# UAF42_AD620___AD8138.net
KiCad netlist of a schematic drawn in EasyEDA Pro
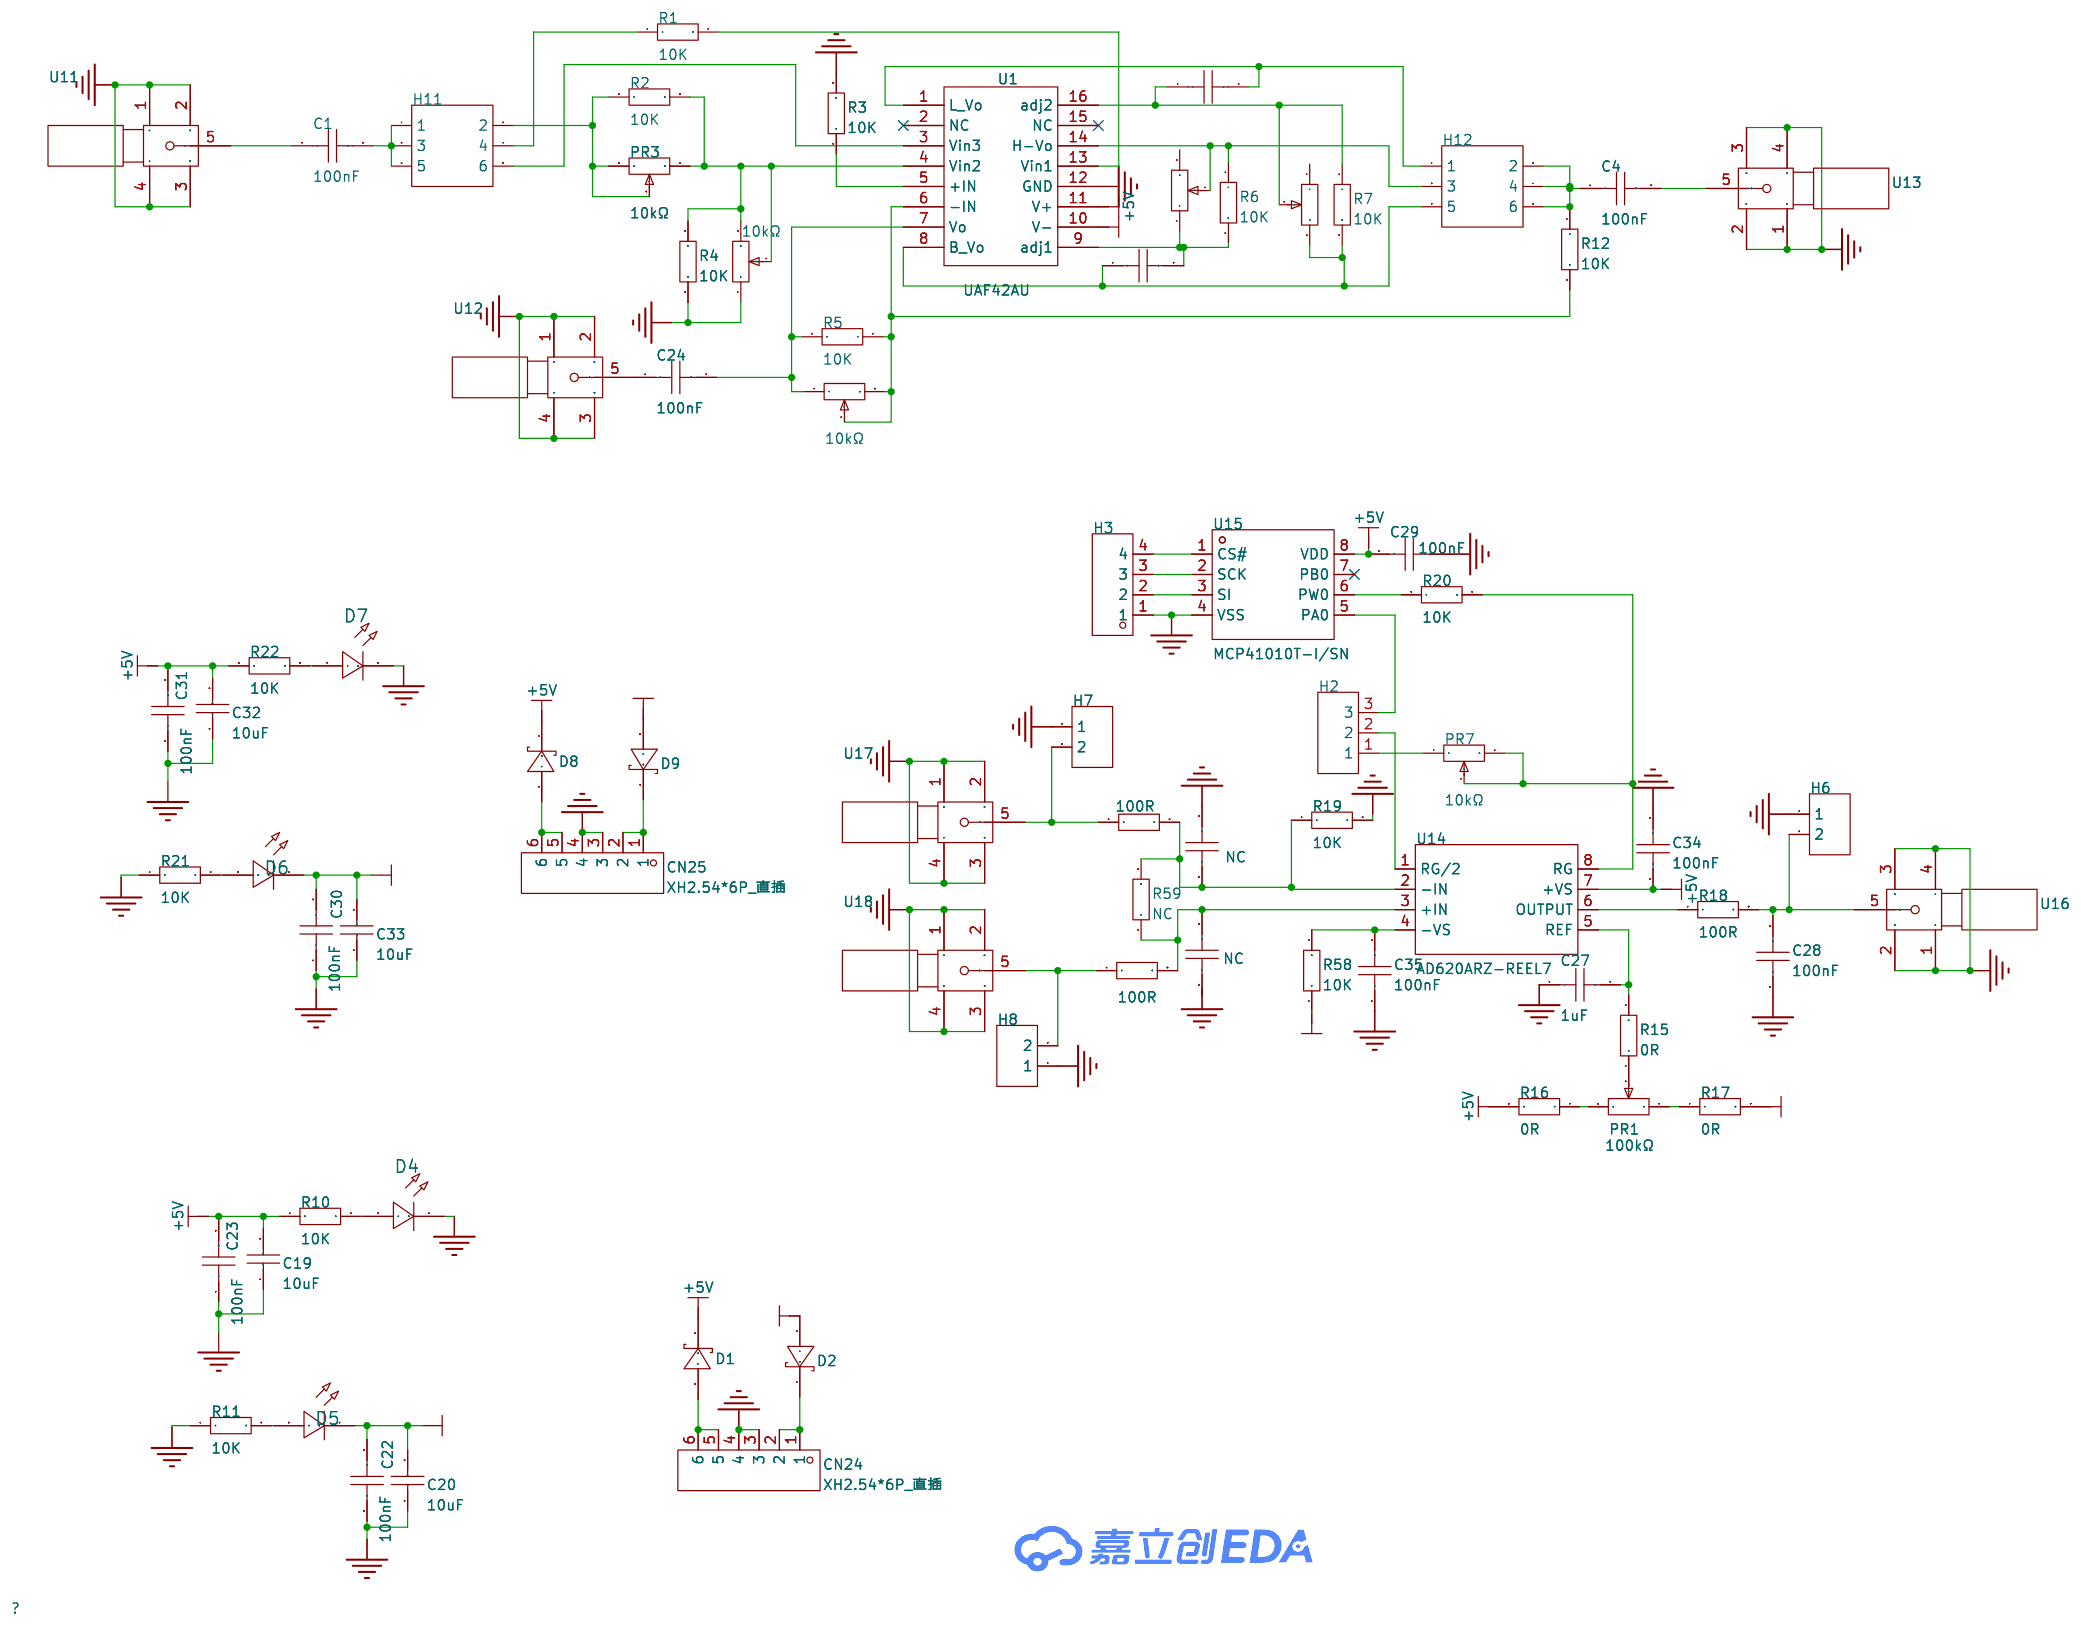
[diagram p0: P1]
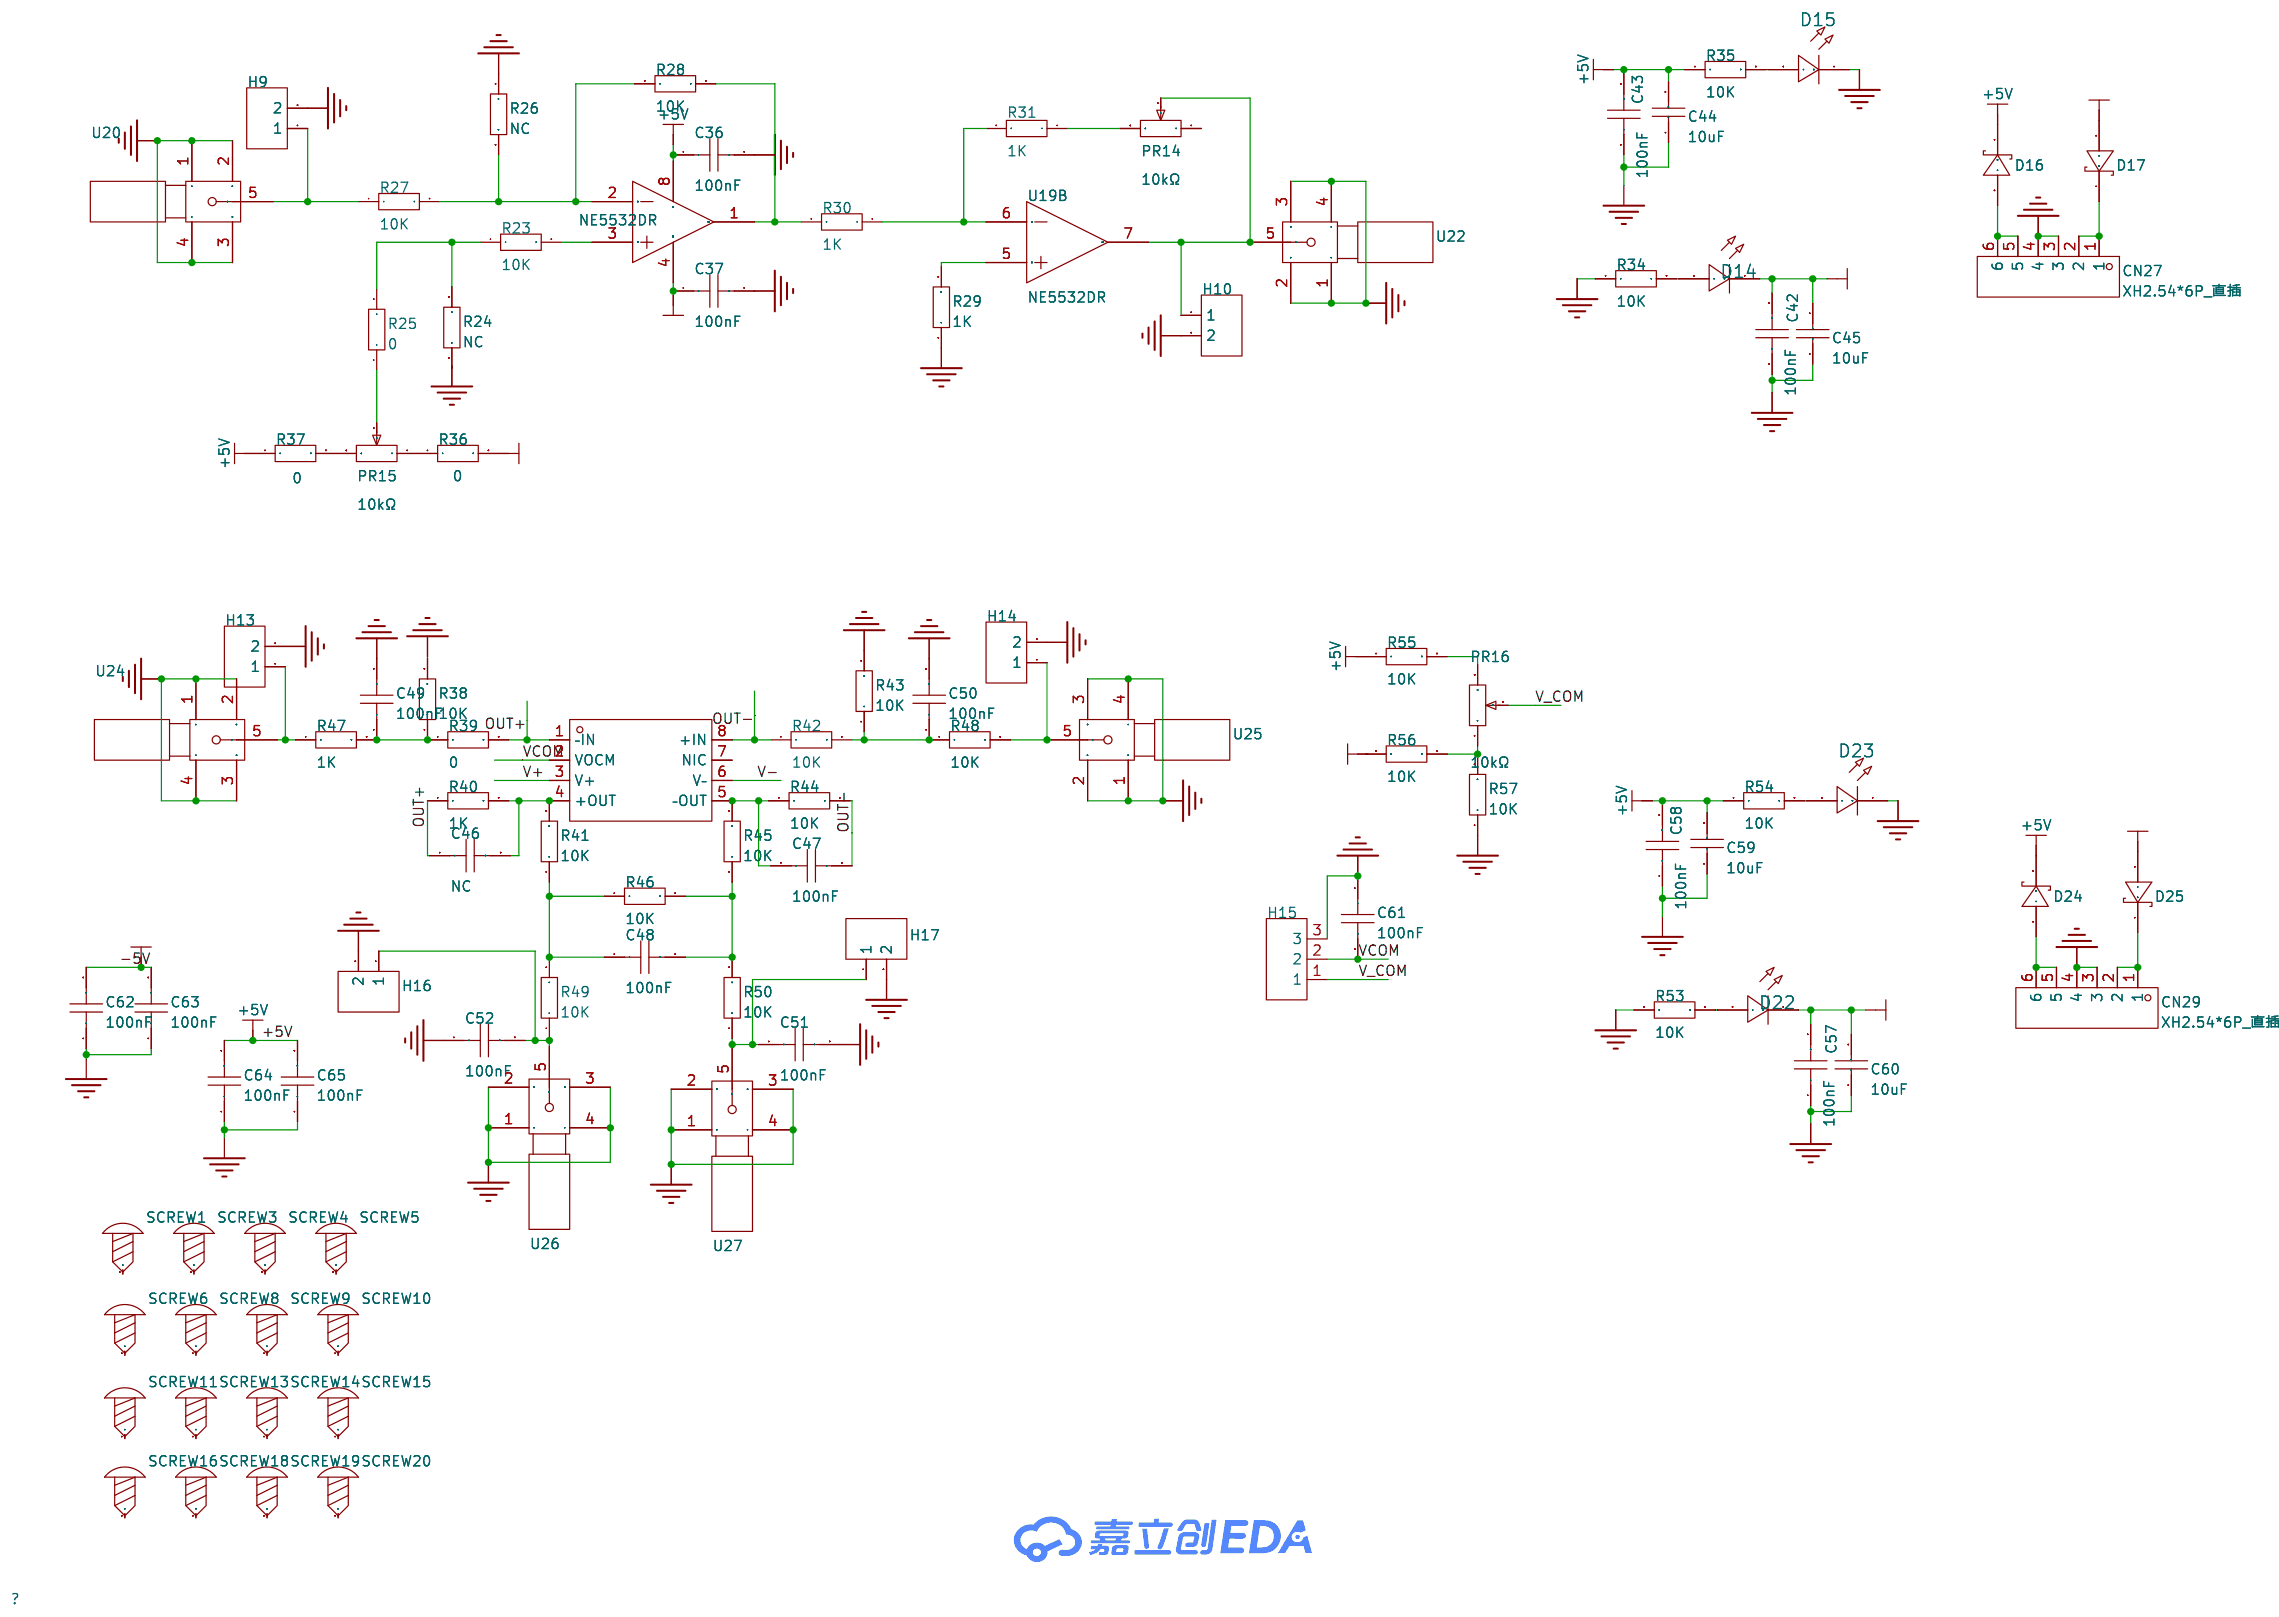
[diagram p1: P2]

(export (version "E")
  (design (tool "Eeschema 10.0.6"))
  (components
    (comp (ref "C1")
      (value "100nF")
      (footprint "easyedapro:C0805")
      (libsource (lib "easyedapro") (part "CapAcitance"))
    )
    (comp (ref "C2")
      (value "100nF")
      (footprint "easyedapro:C0805")
      (libsource (lib "easyedapro") (part "CapAcitance"))
    )
    (comp (ref "C3")
      (value "100nF")
      (footprint "easyedapro:C0805")
      (libsource (lib "easyedapro") (part "CapAcitance"))
    )
    (comp (ref "C4")
      (value "100nF")
      (footprint "easyedapro:C0805")
      (libsource (lib "easyedapro") (part "CapAcitance"))
    )
    (comp (ref "C19")
      (value "10uF")
      (footprint "easyedapro:C1210")
      (description "容值:10uF;精度:±10%;额定电压:25V;材质(温度系数):X7R;")
      (fields
        (field (name "Manufacturer Part") "CL32B106KAJNNNE")
        (field (name "Manufacturer") "SAMSUNG(三星)")
      )
      (libsource (lib "easyedapro") (part "CL32B106KAJNNNE"))
    )
    (comp (ref "C20")
      (value "10uF")
      (footprint "easyedapro:C1210")
      (description "容值:10uF;精度:±10%;额定电压:25V;材质(温度系数):X7R;")
      (fields
        (field (name "Manufacturer Part") "CL32B106KAJNNNE")
        (field (name "Manufacturer") "SAMSUNG(三星)")
      )
      (libsource (lib "easyedapro") (part "CL32B106KAJNNNE"))
    )
    (comp (ref "C22")
      (value "100nF")
      (footprint "easyedapro:C0805")
      (libsource (lib "easyedapro") (part "CapAcitance"))
    )
    (comp (ref "C23")
      (value "100nF")
      (footprint "easyedapro:C0805")
      (libsource (lib "easyedapro") (part "CapAcitance"))
    )
    (comp (ref "C24")
      (value "100nF")
      (footprint "easyedapro:C0805")
      (libsource (lib "easyedapro") (part "CapAcitance"))
    )
    (comp (ref "C25")
      (value "NC")
      (footprint "easyedapro:C0805")
      (libsource (lib "easyedapro") (part "CapAcitance"))
    )
    (comp (ref "C26")
      (value "NC")
      (footprint "easyedapro:C0805")
      (libsource (lib "easyedapro") (part "CapAcitance"))
    )
    (comp (ref "C27")
      (value "1uF")
      (footprint "easyedapro:C0805")
      (libsource (lib "easyedapro") (part "CapAcitance"))
    )
    (comp (ref "C28")
      (value "100nF")
      (footprint "easyedapro:C0805")
      (libsource (lib "easyedapro") (part "CapAcitance"))
    )
    (comp (ref "C29")
      (value "100nF")
      (footprint "easyedapro:C0805")
      (libsource (lib "easyedapro") (part "CapAcitance"))
    )
    (comp (ref "C30")
      (value "100nF")
      (footprint "easyedapro:C0805")
      (libsource (lib "easyedapro") (part "CapAcitance"))
    )
    (comp (ref "C31")
      (value "100nF")
      (footprint "easyedapro:C0805")
      (libsource (lib "easyedapro") (part "CapAcitance"))
    )
    (comp (ref "C32")
      (value "10uF")
      (footprint "easyedapro:C1210")
      (description "容值:10uF;精度:±10%;额定电压:25V;材质(温度系数):X7R;")
      (fields
        (field (name "Manufacturer Part") "CL32B106KAJNNNE")
        (field (name "Manufacturer") "SAMSUNG(三星)")
      )
      (libsource (lib "easyedapro") (part "CL32B106KAJNNNE"))
    )
    (comp (ref "C33")
      (value "10uF")
      (footprint "easyedapro:C1210")
      (description "容值:10uF;精度:±10%;额定电压:25V;材质(温度系数):X7R;")
      (fields
        (field (name "Manufacturer Part") "CL32B106KAJNNNE")
        (field (name "Manufacturer") "SAMSUNG(三星)")
      )
      (libsource (lib "easyedapro") (part "CL32B106KAJNNNE"))
    )
    (comp (ref "C34")
      (value "100nF")
      (footprint "easyedapro:C0805")
      (libsource (lib "easyedapro") (part "CapAcitance"))
    )
    (comp (ref "C35")
      (value "100nF")
      (footprint "easyedapro:C0805")
      (libsource (lib "easyedapro") (part "CapAcitance"))
    )
    (comp (ref "CN24")
      (value "XH2.54*6P_直插")
      (footprint "easyedapro:CONN-TH_XH2.54-6P")
      (libsource (lib "easyedapro") (part "XH2.54*6P_直插"))
    )
    (comp (ref "CN25")
      (value "XH2.54*6P_直插")
      (footprint "easyedapro:CONN-TH_XH2.54-6P")
      (libsource (lib "easyedapro") (part "XH2.54*6P_直插"))
    )
    (comp (ref "D1")
      (value "SD103AWS")
      (footprint "easyedapro:SOD-323_L1.8-W1.3-LS2.5-RD")
      (description "正向压降(Vf):600mV@200mA;直流反向耐压(Vr):40V;整流电流:350mA;")
      (fields (field (name "Manufacturer") "Hottech(合科泰)"))
      (libsource (lib "easyedapro") (part "SD103AWS_C181207"))
    )
    (comp (ref "D2")
      (value "SD103AWS")
      (footprint "easyedapro:SOD-323_L1.8-W1.3-LS2.5-RD")
      (description "正向压降(Vf):600mV@200mA;直流反向耐压(Vr):40V;整流电流:350mA;")
      (fields (field (name "Manufacturer") "Hottech(合科泰)"))
      (libsource (lib "easyedapro") (part "SD103AWS_C181207"))
    )
    (comp (ref "D4")
      (value "~")
      (footprint "easyedapro:LED_0805")
      (libsource (lib "easyedapro") (part "LED_R"))
    )
    (comp (ref "D5")
      (value "~")
      (footprint "easyedapro:LED_0805")
      (libsource (lib "easyedapro") (part "LED_R"))
    )
    (comp (ref "D6")
      (value "~")
      (footprint "easyedapro:LED_0805")
      (libsource (lib "easyedapro") (part "LED_R"))
    )
    (comp (ref "D7")
      (value "~")
      (footprint "easyedapro:LED_0805")
      (libsource (lib "easyedapro") (part "LED_R"))
    )
    (comp (ref "D8")
      (value "SD103AWS")
      (footprint "easyedapro:SOD-323_L1.8-W1.3-LS2.5-RD")
      (description "正向压降(Vf):600mV@200mA;直流反向耐压(Vr):40V;整流电流:350mA;")
      (fields (field (name "Manufacturer") "Hottech(合科泰)"))
      (libsource (lib "easyedapro") (part "SD103AWS_C181207"))
    )
    (comp (ref "D9")
      (value "SD103AWS")
      (footprint "easyedapro:SOD-323_L1.8-W1.3-LS2.5-RD")
      (description "正向压降(Vf):600mV@200mA;直流反向耐压(Vr):40V;整流电流:350mA;")
      (fields (field (name "Manufacturer") "Hottech(合科泰)"))
      (libsource (lib "easyedapro") (part "SD103AWS_C181207"))
    )
    (comp (ref "H2")
      (value "~")
      (footprint "easyedapro:HDR-TH_3P-P2.54-V-F")
      (libsource (lib "easyedapro") (part "PM254V-11-03-H85"))
    )
    (comp (ref "H3")
      (value "~")
      (footprint "easyedapro:HDR-TH_4P-P2.54-V-F")
      (libsource (lib "easyedapro") (part "2.54-1*4P母"))
    )
    (comp (ref "H6")
      (value "~")
      (footprint "easyedapro:HDR-TH_2P-P2.54-V-F")
      (libsource (lib "easyedapro") (part "Header-Female-2.54_1x2"))
    )
    (comp (ref "H7")
      (value "~")
      (footprint "easyedapro:HDR-TH_2P-P2.54-V-F")
      (libsource (lib "easyedapro") (part "Header-Female-2.54_1x2"))
    )
    (comp (ref "H8")
      (value "~")
      (footprint "easyedapro:HDR-TH_2P-P2.54-V-F")
      (libsource (lib "easyedapro") (part "Header-Female-2.54_1x2"))
    )
    (comp (ref "H11")
      (value "~")
      (footprint "easyedapro:HDR-TH_6P-P2.54-V-F-R2-C3-S2.54")
      (libsource (lib "easyedapro") (part "HDR-F-2.54_2x3"))
    )
    (comp (ref "H12")
      (value "~")
      (footprint "easyedapro:HDR-TH_6P-P2.54-V-F-R2-C3-S2.54")
      (libsource (lib "easyedapro") (part "HDR-F-2.54_2x3"))
    )
    (comp (ref "PR1")
      (value "100kΩ")
      (footprint "easyedapro:R_3296")
      (libsource (lib "easyedapro") (part "R_3296"))
    )
    (comp (ref "PR3")
      (value "10kΩ")
      (footprint "easyedapro:R_3296")
      (libsource (lib "easyedapro") (part "R_3296"))
    )
    (comp (ref "PR4")
      (value "10kΩ")
      (footprint "easyedapro:R_3296")
      (libsource (lib "easyedapro") (part "R_3296"))
    )
    (comp (ref "PR6")
      (value "10kΩ")
      (footprint "easyedapro:R_3296")
      (libsource (lib "easyedapro") (part "R_3296"))
    )
    (comp (ref "PR7")
      (value "10kΩ")
      (footprint "easyedapro:R_3296")
      (libsource (lib "easyedapro") (part "R_3296"))
    )
    (comp (ref "PR9")
      (value "10kΩ")
      (footprint "easyedapro:R_3296")
      (libsource (lib "easyedapro") (part "R_3296"))
    )
    (comp (ref "PR13")
      (value "10kΩ")
      (footprint "easyedapro:R_3296")
      (libsource (lib "easyedapro") (part "R_3296"))
    )
    (comp (ref "R1") (value "10K") (footprint "easyedapro:R0805") (libsource (lib "easyedapro") (part "电阻")))
    (comp (ref "R2") (value "10K") (footprint "easyedapro:R0805") (libsource (lib "easyedapro") (part "电阻")))
    (comp (ref "R3") (value "10K") (footprint "easyedapro:R0805") (libsource (lib "easyedapro") (part "电阻")))
    (comp (ref "R4") (value "10K") (footprint "easyedapro:R0805") (libsource (lib "easyedapro") (part "电阻")))
    (comp (ref "R5") (value "10K") (footprint "easyedapro:R0805") (libsource (lib "easyedapro") (part "电阻")))
    (comp (ref "R6") (value "10K") (footprint "easyedapro:R0805") (libsource (lib "easyedapro") (part "电阻")))
    (comp (ref "R7") (value "10K") (footprint "easyedapro:R0805") (libsource (lib "easyedapro") (part "电阻")))
    (comp (ref "R10") (value "10K") (footprint "easyedapro:R0805") (libsource (lib "easyedapro") (part "电阻")))
    (comp (ref "R11") (value "10K") (footprint "easyedapro:R0805") (libsource (lib "easyedapro") (part "电阻")))
    (comp (ref "R12") (value "10K") (footprint "easyedapro:R0805") (libsource (lib "easyedapro") (part "电阻")))
    (comp (ref "R13")
      (value "100R")
      (footprint "easyedapro:R0805")
      (libsource (lib "easyedapro") (part "电阻"))
    )
    (comp (ref "R14")
      (value "100R")
      (footprint "easyedapro:R0805")
      (libsource (lib "easyedapro") (part "电阻"))
    )
    (comp (ref "R15") (value "0R") (footprint "easyedapro:R0805") (libsource (lib "easyedapro") (part "电阻")))
    (comp (ref "R16") (value "0R") (footprint "easyedapro:R0805") (libsource (lib "easyedapro") (part "电阻")))
    (comp (ref "R17") (value "0R") (footprint "easyedapro:R0805") (libsource (lib "easyedapro") (part "电阻")))
    (comp (ref "R18")
      (value "100R")
      (footprint "easyedapro:R0805")
      (libsource (lib "easyedapro") (part "电阻"))
    )
    (comp (ref "R19") (value "10K") (footprint "easyedapro:R0805") (libsource (lib "easyedapro") (part "电阻")))
    (comp (ref "R20") (value "10K") (footprint "easyedapro:R0805") (libsource (lib "easyedapro") (part "电阻")))
    (comp (ref "R21") (value "10K") (footprint "easyedapro:R0805") (libsource (lib "easyedapro") (part "电阻")))
    (comp (ref "R22") (value "10K") (footprint "easyedapro:R0805") (libsource (lib "easyedapro") (part "电阻")))
    (comp (ref "R58") (value "10K") (footprint "easyedapro:R0805") (libsource (lib "easyedapro") (part "电阻")))
    (comp (ref "R59") (value "NC") (footprint "easyedapro:R0805") (libsource (lib "easyedapro") (part "电阻")))
    (comp (ref "U1")
      (value "UAF42AU")
      (footprint "easyedapro:SOIC-16_L10.3-W7.5-P1.27-LS10.3-BL")
      (description "分辨率:-;工作电压:6V~18V;接口类型:-;")
      (fields (field (name "Manufacturer") "TI(德州仪器)"))
      (libsource (lib "easyedapro") (part "UAF42AU"))
    )
    (comp (ref "U11") (value "~") (footprint "easyedapro:SMA") (libsource (lib "easyedapro") (part "SMA")))
    (comp (ref "U12") (value "~") (footprint "easyedapro:SMA") (libsource (lib "easyedapro") (part "SMA")))
    (comp (ref "U13") (value "~") (footprint "easyedapro:SMA") (libsource (lib "easyedapro") (part "SMA")))
    (comp (ref "U14")
      (value "AD620ARZ-REEL7")
      (footprint "easyedapro:SOIC-8_L5.0-W4.0-P1.27-LS6.0-BL")
      (description "放大器数:单路;输入偏置电流(Ib):500pA;输入失调电压(Vos):30uV;增益带宽积(GBP):-;压摆率(SR):1.2V/us;带宽(-3db):1MHz;")
      (fields (field (name "Manufacturer") "ADI(亚德诺)"))
      (libsource (lib "easyedapro") (part "AD620ARZ-REEL"))
    )
    (comp (ref "U15")
      (value "MCP41010T-I/SN")
      (footprint "easyedapro:SOIC-8_L4.9-W3.9-P1.27-LS6.0-BL")
      (description "电阻值(欧姆):10kΩ;精度:±20%;供电电压:2.7V~5.5V;接口类型:SPI;")
      (fields (field (name "Manufacturer") "MICROCHIP(美国微芯)"))
      (libsource (lib "easyedapro") (part "MCP41010T-I/SN"))
    )
    (comp (ref "U16") (value "~") (footprint "easyedapro:SMA") (libsource (lib "easyedapro") (part "SMA")))
    (comp (ref "U17") (value "~") (footprint "easyedapro:SMA") (libsource (lib "easyedapro") (part "SMA")))
    (comp (ref "U18") (value "~") (footprint "easyedapro:SMA") (libsource (lib "easyedapro") (part "SMA")))
    (comp (ref "C36")
      (value "100nF")
      (footprint "easyedapro:C0805")
      (libsource (lib "easyedapro") (part "CapAcitance"))
    )
    (comp (ref "C37")
      (value "100nF")
      (footprint "easyedapro:C0805")
      (libsource (lib "easyedapro") (part "CapAcitance"))
    )
    (comp (ref "C42")
      (value "100nF")
      (footprint "easyedapro:C0805")
      (libsource (lib "easyedapro") (part "CapAcitance"))
    )
    (comp (ref "C43")
      (value "100nF")
      (footprint "easyedapro:C0805")
      (libsource (lib "easyedapro") (part "CapAcitance"))
    )
    (comp (ref "C44")
      (value "10uF")
      (footprint "easyedapro:C1210")
      (description "容值:10uF;精度:±10%;额定电压:25V;材质(温度系数):X7R;")
      (fields
        (field (name "Manufacturer Part") "CL32B106KAJNNNE")
        (field (name "Manufacturer") "SAMSUNG(三星)")
      )
      (libsource (lib "easyedapro") (part "CL32B106KAJNNNE"))
    )
    (comp (ref "C45")
      (value "10uF")
      (footprint "easyedapro:C1210")
      (description "容值:10uF;精度:±10%;额定电压:25V;材质(温度系数):X7R;")
      (fields
        (field (name "Manufacturer Part") "CL32B106KAJNNNE")
        (field (name "Manufacturer") "SAMSUNG(三星)")
      )
      (libsource (lib "easyedapro") (part "CL32B106KAJNNNE"))
    )
    (comp (ref "C46")
      (value "NC")
      (footprint "easyedapro:C0805")
      (libsource (lib "easyedapro") (part "CapAcitance"))
    )
    (comp (ref "C47")
      (value "100nF")
      (footprint "easyedapro:C0805")
      (libsource (lib "easyedapro") (part "CapAcitance"))
    )
    (comp (ref "C48")
      (value "100nF")
      (footprint "easyedapro:C0805")
      (libsource (lib "easyedapro") (part "CapAcitance"))
    )
    (comp (ref "C49")
      (value "100nF")
      (footprint "easyedapro:C0805")
      (libsource (lib "easyedapro") (part "CapAcitance"))
    )
    (comp (ref "C50")
      (value "100nF")
      (footprint "easyedapro:C0805")
      (libsource (lib "easyedapro") (part "CapAcitance"))
    )
    (comp (ref "C51")
      (value "100nF")
      (footprint "easyedapro:C0805")
      (libsource (lib "easyedapro") (part "CapAcitance"))
    )
    (comp (ref "C52")
      (value "100nF")
      (footprint "easyedapro:C0805")
      (libsource (lib "easyedapro") (part "CapAcitance"))
    )
    (comp (ref "C57")
      (value "100nF")
      (footprint "easyedapro:C0805")
      (libsource (lib "easyedapro") (part "CapAcitance"))
    )
    (comp (ref "C58")
      (value "100nF")
      (footprint "easyedapro:C0805")
      (libsource (lib "easyedapro") (part "CapAcitance"))
    )
    (comp (ref "C59")
      (value "10uF")
      (footprint "easyedapro:C1210")
      (description "容值:10uF;精度:±10%;额定电压:25V;材质(温度系数):X7R;")
      (fields
        (field (name "Manufacturer Part") "CL32B106KAJNNNE")
        (field (name "Manufacturer") "SAMSUNG(三星)")
      )
      (libsource (lib "easyedapro") (part "CL32B106KAJNNNE"))
    )
    (comp (ref "C60")
      (value "10uF")
      (footprint "easyedapro:C1210")
      (description "容值:10uF;精度:±10%;额定电压:25V;材质(温度系数):X7R;")
      (fields
        (field (name "Manufacturer Part") "CL32B106KAJNNNE")
        (field (name "Manufacturer") "SAMSUNG(三星)")
      )
      (libsource (lib "easyedapro") (part "CL32B106KAJNNNE"))
    )
    (comp (ref "C61")
      (value "100nF")
      (footprint "easyedapro:C0805")
      (libsource (lib "easyedapro") (part "CapAcitance"))
    )
    (comp (ref "C62")
      (value "100nF")
      (footprint "easyedapro:C0805")
      (libsource (lib "easyedapro") (part "CapAcitance"))
    )
    (comp (ref "C63")
      (value "100nF")
      (footprint "easyedapro:C0805")
      (libsource (lib "easyedapro") (part "CapAcitance"))
    )
    (comp (ref "C64")
      (value "100nF")
      (footprint "easyedapro:C0805")
      (libsource (lib "easyedapro") (part "CapAcitance"))
    )
    (comp (ref "C65")
      (value "100nF")
      (footprint "easyedapro:C0805")
      (libsource (lib "easyedapro") (part "CapAcitance"))
    )
    (comp (ref "CN27")
      (value "XH2.54*6P_直插")
      (footprint "easyedapro:CONN-TH_XH2.54-6P")
      (libsource (lib "easyedapro") (part "XH2.54*6P_直插"))
    )
    (comp (ref "CN29")
      (value "XH2.54*6P_直插")
      (footprint "easyedapro:CONN-TH_XH2.54-6P")
      (libsource (lib "easyedapro") (part "XH2.54*6P_直插"))
    )
    (comp (ref "D14")
      (value "~")
      (footprint "easyedapro:LED_0805")
      (libsource (lib "easyedapro") (part "LED_R"))
    )
    (comp (ref "D15")
      (value "~")
      (footprint "easyedapro:LED_0805")
      (libsource (lib "easyedapro") (part "LED_R"))
    )
    (comp (ref "D16")
      (value "SD103AWS")
      (footprint "easyedapro:SOD-323_L1.8-W1.3-LS2.5-RD")
      (description "正向压降(Vf):600mV@200mA;直流反向耐压(Vr):40V;整流电流:350mA;")
      (fields (field (name "Manufacturer") "Hottech(合科泰)"))
      (libsource (lib "easyedapro") (part "SD103AWS_C181207"))
    )
    (comp (ref "D17")
      (value "SD103AWS")
      (footprint "easyedapro:SOD-323_L1.8-W1.3-LS2.5-RD")
      (description "正向压降(Vf):600mV@200mA;直流反向耐压(Vr):40V;整流电流:350mA;")
      (fields (field (name "Manufacturer") "Hottech(合科泰)"))
      (libsource (lib "easyedapro") (part "SD103AWS_C181207"))
    )
    (comp (ref "D22")
      (value "~")
      (footprint "easyedapro:LED_0805")
      (libsource (lib "easyedapro") (part "LED_R"))
    )
    (comp (ref "D23")
      (value "~")
      (footprint "easyedapro:LED_0805")
      (libsource (lib "easyedapro") (part "LED_R"))
    )
    (comp (ref "D24")
      (value "SD103AWS")
      (footprint "easyedapro:SOD-323_L1.8-W1.3-LS2.5-RD")
      (description "正向压降(Vf):600mV@200mA;直流反向耐压(Vr):40V;整流电流:350mA;")
      (fields (field (name "Manufacturer") "Hottech(合科泰)"))
      (libsource (lib "easyedapro") (part "SD103AWS_C181207"))
    )
    (comp (ref "D25")
      (value "SD103AWS")
      (footprint "easyedapro:SOD-323_L1.8-W1.3-LS2.5-RD")
      (description "正向压降(Vf):600mV@200mA;直流反向耐压(Vr):40V;整流电流:350mA;")
      (fields (field (name "Manufacturer") "Hottech(合科泰)"))
      (libsource (lib "easyedapro") (part "SD103AWS_C181207"))
    )
    (comp (ref "H9")
      (value "~")
      (footprint "easyedapro:HDR-TH_2P-P2.54-V-F")
      (libsource (lib "easyedapro") (part "Header-Female-2.54_1x2"))
    )
    (comp (ref "H10")
      (value "~")
      (footprint "easyedapro:HDR-TH_2P-P2.54-V-F")
      (libsource (lib "easyedapro") (part "Header-Female-2.54_1x2"))
    )
    (comp (ref "H13")
      (value "~")
      (footprint "easyedapro:HDR-TH_2P-P2.54-V-F")
      (libsource (lib "easyedapro") (part "Header-Female-2.54_1x2"))
    )
    (comp (ref "H14")
      (value "~")
      (footprint "easyedapro:HDR-TH_2P-P2.54-V-F")
      (libsource (lib "easyedapro") (part "Header-Female-2.54_1x2"))
    )
    (comp (ref "H15")
      (value "~")
      (footprint "easyedapro:HDR-TH_3P-P2.54-V-F")
      (libsource (lib "easyedapro") (part "PM254V-11-03-H85"))
    )
    (comp (ref "H16")
      (value "~")
      (footprint "easyedapro:HDR-TH_2P-P2.54-V-F")
      (libsource (lib "easyedapro") (part "Header-Female-2.54_1x2"))
    )
    (comp (ref "H17")
      (value "~")
      (footprint "easyedapro:HDR-TH_2P-P2.54-V-F")
      (libsource (lib "easyedapro") (part "Header-Female-2.54_1x2"))
    )
    (comp (ref "PR14")
      (value "10kΩ")
      (footprint "easyedapro:R_3296")
      (libsource (lib "easyedapro") (part "R_3296"))
    )
    (comp (ref "PR15")
      (value "10kΩ")
      (footprint "easyedapro:R_3296")
      (libsource (lib "easyedapro") (part "R_3296"))
    )
    (comp (ref "PR16")
      (value "10kΩ")
      (footprint "easyedapro:R_3296")
      (libsource (lib "easyedapro") (part "R_3296"))
    )
    (comp (ref "R23") (value "10K") (footprint "easyedapro:R0805") (libsource (lib "easyedapro") (part "电阻")))
    (comp (ref "R24") (value "NC") (footprint "easyedapro:R0805") (libsource (lib "easyedapro") (part "电阻")))
    (comp (ref "R25") (value "0") (footprint "easyedapro:R0805") (libsource (lib "easyedapro") (part "电阻")))
    (comp (ref "R26") (value "NC") (footprint "easyedapro:R0805") (libsource (lib "easyedapro") (part "电阻")))
    (comp (ref "R27") (value "10K") (footprint "easyedapro:R0805") (libsource (lib "easyedapro") (part "电阻")))
    (comp (ref "R28") (value "10K") (footprint "easyedapro:R0805") (libsource (lib "easyedapro") (part "电阻")))
    (comp (ref "R29") (value "1K") (footprint "easyedapro:R0805") (libsource (lib "easyedapro") (part "电阻")))
    (comp (ref "R30") (value "1K") (footprint "easyedapro:R0805") (libsource (lib "easyedapro") (part "电阻")))
    (comp (ref "R31") (value "1K") (footprint "easyedapro:R0805") (libsource (lib "easyedapro") (part "电阻")))
    (comp (ref "R34") (value "10K") (footprint "easyedapro:R0805") (libsource (lib "easyedapro") (part "电阻")))
    (comp (ref "R35") (value "10K") (footprint "easyedapro:R0805") (libsource (lib "easyedapro") (part "电阻")))
    (comp (ref "R36") (value "0") (footprint "easyedapro:R0805") (libsource (lib "easyedapro") (part "电阻")))
    (comp (ref "R37") (value "0") (footprint "easyedapro:R0805") (libsource (lib "easyedapro") (part "电阻")))
    (comp (ref "R38") (value "10K") (footprint "easyedapro:R0805") (libsource (lib "easyedapro") (part "电阻")))
    (comp (ref "R39") (value "0") (footprint "easyedapro:R0805") (libsource (lib "easyedapro") (part "电阻")))
    (comp (ref "R40") (value "1K") (footprint "easyedapro:R0805") (libsource (lib "easyedapro") (part "电阻")))
    (comp (ref "R41") (value "10K") (footprint "easyedapro:R0805") (libsource (lib "easyedapro") (part "电阻")))
    (comp (ref "R42") (value "10K") (footprint "easyedapro:R0805") (libsource (lib "easyedapro") (part "电阻")))
    (comp (ref "R43") (value "10K") (footprint "easyedapro:R0805") (libsource (lib "easyedapro") (part "电阻")))
    (comp (ref "R44") (value "10K") (footprint "easyedapro:R0805") (libsource (lib "easyedapro") (part "电阻")))
    (comp (ref "R45") (value "10K") (footprint "easyedapro:R0805") (libsource (lib "easyedapro") (part "电阻")))
    (comp (ref "R46") (value "10K") (footprint "easyedapro:R0805") (libsource (lib "easyedapro") (part "电阻")))
    (comp (ref "R47") (value "1K") (footprint "easyedapro:R0805") (libsource (lib "easyedapro") (part "电阻")))
    (comp (ref "R48") (value "10K") (footprint "easyedapro:R0805") (libsource (lib "easyedapro") (part "电阻")))
    (comp (ref "R49") (value "10K") (footprint "easyedapro:R0805") (libsource (lib "easyedapro") (part "电阻")))
    (comp (ref "R50") (value "10K") (footprint "easyedapro:R0805") (libsource (lib "easyedapro") (part "电阻")))
    (comp (ref "R53") (value "10K") (footprint "easyedapro:R0805") (libsource (lib "easyedapro") (part "电阻")))
    (comp (ref "R54") (value "10K") (footprint "easyedapro:R0805") (libsource (lib "easyedapro") (part "电阻")))
    (comp (ref "R55") (value "10K") (footprint "easyedapro:R0805") (libsource (lib "easyedapro") (part "电阻")))
    (comp (ref "R56") (value "10K") (footprint "easyedapro:R0805") (libsource (lib "easyedapro") (part "电阻")))
    (comp (ref "R57") (value "10K") (footprint "easyedapro:R0805") (libsource (lib "easyedapro") (part "电阻")))
    (comp (ref "SCREW1")
      (value "~")
      (footprint "easyedapro:M3螺丝")
      (libsource (lib "easyedapro") (part "螺丝孔"))
    )
    (comp (ref "SCREW3")
      (value "~")
      (footprint "easyedapro:M3螺丝")
      (libsource (lib "easyedapro") (part "螺丝孔"))
    )
    (comp (ref "SCREW4")
      (value "~")
      (footprint "easyedapro:M3螺丝")
      (libsource (lib "easyedapro") (part "螺丝孔"))
    )
    (comp (ref "SCREW5")
      (value "~")
      (footprint "easyedapro:M3螺丝")
      (libsource (lib "easyedapro") (part "螺丝孔"))
    )
    (comp (ref "SCREW6")
      (value "~")
      (footprint "easyedapro:M3螺丝")
      (libsource (lib "easyedapro") (part "螺丝孔"))
    )
    (comp (ref "SCREW8")
      (value "~")
      (footprint "easyedapro:M3螺丝")
      (libsource (lib "easyedapro") (part "螺丝孔"))
    )
    (comp (ref "SCREW9")
      (value "~")
      (footprint "easyedapro:M3螺丝")
      (libsource (lib "easyedapro") (part "螺丝孔"))
    )
    (comp (ref "SCREW10")
      (value "~")
      (footprint "easyedapro:M3螺丝")
      (libsource (lib "easyedapro") (part "螺丝孔"))
    )
    (comp (ref "SCREW11")
      (value "~")
      (footprint "easyedapro:M3螺丝")
      (libsource (lib "easyedapro") (part "螺丝孔"))
    )
    (comp (ref "SCREW13")
      (value "~")
      (footprint "easyedapro:M3螺丝")
      (libsource (lib "easyedapro") (part "螺丝孔"))
    )
    (comp (ref "SCREW14")
      (value "~")
      (footprint "easyedapro:M3螺丝")
      (libsource (lib "easyedapro") (part "螺丝孔"))
    )
    (comp (ref "SCREW15")
      (value "~")
      (footprint "easyedapro:M3螺丝")
      (libsource (lib "easyedapro") (part "螺丝孔"))
    )
    (comp (ref "SCREW16")
      (value "~")
      (footprint "easyedapro:M3螺丝")
      (libsource (lib "easyedapro") (part "螺丝孔"))
    )
    (comp (ref "SCREW18")
      (value "~")
      (footprint "easyedapro:M3螺丝")
      (libsource (lib "easyedapro") (part "螺丝孔"))
    )
    (comp (ref "SCREW19")
      (value "~")
      (footprint "easyedapro:M3螺丝")
      (libsource (lib "easyedapro") (part "螺丝孔"))
    )
    (comp (ref "SCREW20")
      (value "~")
      (footprint "easyedapro:M3螺丝")
      (libsource (lib "easyedapro") (part "螺丝孔"))
    )
    (comp (ref "U19")
      (value "NE5532DR")
      (footprint "easyedapro:SOIC-8_L4.9-W3.9-P1.27-LS6.0-BL")
      (description "放大器数:双路;增益带宽积(GBP):10MHz;输入偏置电流(Ib):200nA;压摆率(SR):9V/us;带宽(-3db):-;")
      (fields (field (name "Manufacturer") "TI(德州仪器)"))
      (libsource (lib "easyedapro") (part "NE5532DR"))
    )
    (comp (ref "U20") (value "~") (footprint "easyedapro:SMA") (libsource (lib "easyedapro") (part "SMA")))
    (comp (ref "U22") (value "~") (footprint "easyedapro:SMA") (libsource (lib "easyedapro") (part "SMA")))
    (comp (ref "U23")
      (value "AD8138ARZ-RL")
      (footprint "easyedapro:SOIC-8_L5.0-W4.0-P1.27-LS6.0-BL")
      (description "放大器数:单路;共模抑制比(CMRR):77dB;输入偏置电流(Ib):500nA;输入失调电压(Vos):1mV;压摆率(SR):1150V/us;带宽(-3db):320MHz;")
      (fields (field (name "Manufacturer") "ADI(亚德诺)"))
      (libsource (lib "easyedapro") (part "AD8138ARZ-RL"))
    )
    (comp (ref "U24") (value "~") (footprint "easyedapro:SMA") (libsource (lib "easyedapro") (part "SMA")))
    (comp (ref "U25") (value "~") (footprint "easyedapro:SMA") (libsource (lib "easyedapro") (part "SMA")))
    (comp (ref "U26") (value "~") (footprint "easyedapro:SMA") (libsource (lib "easyedapro") (part "SMA")))
    (comp (ref "U27") (value "~") (footprint "easyedapro:SMA") (libsource (lib "easyedapro") (part "SMA")))
  )
  (nets
    (net (code "1") (name "+5V") (class "Default")
      (node (ref "C19") (pin "2") (pinfunction "2_2") (pintype "input"))
      (node (ref "C23") (pin "2") (pinfunction "2_2") (pintype "input"))
      (node (ref "C29") (pin "1") (pinfunction "1_1") (pintype "input"))
      (node (ref "C31") (pin "2") (pinfunction "2_2") (pintype "input"))
      (node (ref "C32") (pin "2") (pinfunction "2_2") (pintype "input"))
      (node (ref "C34") (pin "1") (pinfunction "1_1") (pintype "input"))
      (node (ref "C36") (pin "1") (pinfunction "1_1") (pintype "input"))
      (node (ref "C43") (pin "2") (pinfunction "2_2") (pintype "input"))
      (node (ref "C44") (pin "2") (pinfunction "2_2") (pintype "input"))
      (node (ref "C58") (pin "2") (pinfunction "2_2") (pintype "input"))
      (node (ref "C59") (pin "2") (pinfunction "2_2") (pintype "input"))
      (node (ref "C64") (pin "2") (pinfunction "2_2") (pintype "input"))
      (node (ref "C65") (pin "2") (pinfunction "2_2") (pintype "input"))
      (node (ref "D1") (pin "1") (pinfunction "C_1") (pintype "unspecified"))
      (node (ref "D16") (pin "1") (pinfunction "C_1") (pintype "unspecified"))
      (node (ref "D24") (pin "1") (pinfunction "C_1") (pintype "unspecified"))
      (node (ref "D8") (pin "1") (pinfunction "C_1") (pintype "unspecified"))
      (node (ref "R10") (pin "1") (pinfunction "1_1") (pintype "input"))
      (node (ref "R16") (pin "2") (pinfunction "2_2") (pintype "input"))
      (node (ref "R22") (pin "1") (pinfunction "1_1") (pintype "input"))
      (node (ref "R35") (pin "1") (pinfunction "1_1") (pintype "input"))
      (node (ref "R37") (pin "1") (pinfunction "1_1") (pintype "input"))
      (node (ref "R54") (pin "1") (pinfunction "1_1") (pintype "input"))
      (node (ref "R55") (pin "1") (pinfunction "1_1") (pintype "input"))
      (node (ref "U1") (pin "11") (pinfunction "V+_11") (pintype "input"))
      (node (ref "U14") (pin "7") (pinfunction "+VS_7") (pintype "unspecified"))
      (node (ref "U15") (pin "8") (pinfunction "VDD_8") (pintype "unspecified"))
      (node (ref "U19") (pin "8") (pinfunction "VCC+_8") (pintype "unspecified"))
    )
    (net (code "2") (name "-5V") (class "Default")
      (node (ref "C20") (pin "2") (pinfunction "2_2") (pintype "input"))
      (node (ref "C22") (pin "2") (pinfunction "2_2") (pintype "input"))
      (node (ref "C30") (pin "2") (pinfunction "2_2") (pintype "input"))
      (node (ref "C33") (pin "2") (pinfunction "2_2") (pintype "input"))
      (node (ref "C37") (pin "1") (pinfunction "1_1") (pintype "input"))
      (node (ref "C42") (pin "2") (pinfunction "2_2") (pintype "input"))
      (node (ref "C45") (pin "2") (pinfunction "2_2") (pintype "input"))
      (node (ref "C57") (pin "2") (pinfunction "2_2") (pintype "input"))
      (node (ref "C60") (pin "2") (pinfunction "2_2") (pintype "input"))
      (node (ref "C62") (pin "2") (pinfunction "2_2") (pintype "input"))
      (node (ref "C63") (pin "2") (pinfunction "2_2") (pintype "input"))
      (node (ref "D14") (pin "1") (pinfunction "C_1") (pintype "input"))
      (node (ref "D17") (pin "2") (pinfunction "A_2") (pintype "unspecified"))
      (node (ref "D2") (pin "2") (pinfunction "A_2") (pintype "unspecified"))
      (node (ref "D22") (pin "1") (pinfunction "C_1") (pintype "input"))
      (node (ref "D25") (pin "2") (pinfunction "A_2") (pintype "unspecified"))
      (node (ref "D5") (pin "1") (pinfunction "C_1") (pintype "input"))
      (node (ref "D6") (pin "1") (pinfunction "C_1") (pintype "input"))
      (node (ref "D9") (pin "2") (pinfunction "A_2") (pintype "unspecified"))
      (node (ref "R17") (pin "2") (pinfunction "2_2") (pintype "input"))
      (node (ref "R36") (pin "2") (pinfunction "2_2") (pintype "input"))
      (node (ref "R56") (pin "2") (pinfunction "2_2") (pintype "input"))
      (node (ref "R58") (pin "1") (pinfunction "1_1") (pintype "input"))
      (node (ref "U1") (pin "10") (pinfunction "V-_10") (pintype "input"))
      (node (ref "U19") (pin "4") (pinfunction "VCC-/GND_4") (pintype "unspecified"))
    )
    (net (code "3") (name "GND") (class "Default")
      (node (ref "C19") (pin "1") (pinfunction "1_1") (pintype "input"))
      (node (ref "C20") (pin "1") (pinfunction "1_1") (pintype "input"))
      (node (ref "C22") (pin "1") (pinfunction "1_1") (pintype "input"))
      (node (ref "C23") (pin "1") (pinfunction "1_1") (pintype "input"))
      (node (ref "C25") (pin "2") (pinfunction "2_2") (pintype "input"))
      (node (ref "C26") (pin "1") (pinfunction "1_1") (pintype "input"))
      (node (ref "C27") (pin "1") (pinfunction "1_1") (pintype "input"))
      (node (ref "C28") (pin "1") (pinfunction "1_1") (pintype "input"))
      (node (ref "C29") (pin "2") (pinfunction "2_2") (pintype "input"))
      (node (ref "C30") (pin "1") (pinfunction "1_1") (pintype "input"))
      (node (ref "C31") (pin "1") (pinfunction "1_1") (pintype "input"))
      (node (ref "C32") (pin "1") (pinfunction "1_1") (pintype "input"))
      (node (ref "C33") (pin "1") (pinfunction "1_1") (pintype "input"))
      (node (ref "C34") (pin "2") (pinfunction "2_2") (pintype "input"))
      (node (ref "C35") (pin "1") (pinfunction "1_1") (pintype "input"))
      (node (ref "C36") (pin "2") (pinfunction "2_2") (pintype "input"))
      (node (ref "C37") (pin "2") (pinfunction "2_2") (pintype "input"))
      (node (ref "C42") (pin "1") (pinfunction "1_1") (pintype "input"))
      (node (ref "C43") (pin "1") (pinfunction "1_1") (pintype "input"))
      (node (ref "C44") (pin "1") (pinfunction "1_1") (pintype "input"))
      (node (ref "C45") (pin "1") (pinfunction "1_1") (pintype "input"))
      (node (ref "C49") (pin "2") (pinfunction "2_2") (pintype "input"))
      (node (ref "C50") (pin "2") (pinfunction "2_2") (pintype "input"))
      (node (ref "C51") (pin "2") (pinfunction "2_2") (pintype "input"))
      (node (ref "C52") (pin "1") (pinfunction "1_1") (pintype "input"))
      (node (ref "C57") (pin "1") (pinfunction "1_1") (pintype "input"))
      (node (ref "C58") (pin "1") (pinfunction "1_1") (pintype "input"))
      (node (ref "C59") (pin "1") (pinfunction "1_1") (pintype "input"))
      (node (ref "C60") (pin "1") (pinfunction "1_1") (pintype "input"))
      (node (ref "C61") (pin "1") (pinfunction "1_1") (pintype "input"))
      (node (ref "C62") (pin "1") (pinfunction "1_1") (pintype "input"))
      (node (ref "C63") (pin "1") (pinfunction "1_1") (pintype "input"))
      (node (ref "C64") (pin "1") (pinfunction "1_1") (pintype "input"))
      (node (ref "C65") (pin "1") (pinfunction "1_1") (pintype "input"))
      (node (ref "CN24") (pin "3") (pinfunction "3_3") (pintype "unspecified"))
      (node (ref "CN24") (pin "4") (pinfunction "4_4") (pintype "unspecified"))
      (node (ref "CN25") (pin "3") (pinfunction "3_3") (pintype "unspecified"))
      (node (ref "CN25") (pin "4") (pinfunction "4_4") (pintype "unspecified"))
      (node (ref "CN27") (pin "3") (pinfunction "3_3") (pintype "unspecified"))
      (node (ref "CN27") (pin "4") (pinfunction "4_4") (pintype "unspecified"))
      (node (ref "CN29") (pin "3") (pinfunction "3_3") (pintype "unspecified"))
      (node (ref "CN29") (pin "4") (pinfunction "4_4") (pintype "unspecified"))
      (node (ref "D15") (pin "1") (pinfunction "C_1") (pintype "input"))
      (node (ref "D23") (pin "1") (pinfunction "C_1") (pintype "input"))
      (node (ref "D4") (pin "1") (pinfunction "C_1") (pintype "input"))
      (node (ref "D7") (pin "1") (pinfunction "C_1") (pintype "input"))
      (node (ref "H10") (pin "2") (pinfunction "2_2") (pintype "input"))
      (node (ref "H13") (pin "2") (pinfunction "2_2") (pintype "input"))
      (node (ref "H14") (pin "2") (pinfunction "2_2") (pintype "input"))
      (node (ref "H15") (pin "3") (pinfunction "3_3") (pintype "unspecified"))
      (node (ref "H16") (pin "2") (pinfunction "2_2") (pintype "input"))
      (node (ref "H17") (pin "2") (pinfunction "2_2") (pintype "input"))
      (node (ref "H3") (pin "1") (pinfunction "1_1") (pintype "unspecified"))
      (node (ref "H6") (pin "1") (pinfunction "1_1") (pintype "input"))
      (node (ref "H7") (pin "1") (pinfunction "1_1") (pintype "input"))
      (node (ref "H8") (pin "1") (pinfunction "1_1") (pintype "input"))
      (node (ref "H9") (pin "2") (pinfunction "2_2") (pintype "input"))
      (node (ref "PR9") (pin "1") (pinfunction "1_1") (pintype "input"))
      (node (ref "R11") (pin "1") (pinfunction "1_1") (pintype "input"))
      (node (ref "R19") (pin "2") (pinfunction "2_2") (pintype "input"))
      (node (ref "R21") (pin "1") (pinfunction "1_1") (pintype "input"))
      (node (ref "R24") (pin "1") (pinfunction "1_1") (pintype "input"))
      (node (ref "R26") (pin "1") (pinfunction "1_1") (pintype "input"))
      (node (ref "R29") (pin "1") (pinfunction "1_1") (pintype "input"))
      (node (ref "R3") (pin "2") (pinfunction "2_2") (pintype "input"))
      (node (ref "R34") (pin "1") (pinfunction "1_1") (pintype "input"))
      (node (ref "R38") (pin "2") (pinfunction "2_2") (pintype "input"))
      (node (ref "R4") (pin "1") (pinfunction "1_1") (pintype "input"))
      (node (ref "R43") (pin "2") (pinfunction "2_2") (pintype "input"))
      (node (ref "R53") (pin "1") (pinfunction "1_1") (pintype "input"))
      (node (ref "R57") (pin "1") (pinfunction "1_1") (pintype "input"))
      (node (ref "U1") (pin "12") (pinfunction "GND_12") (pintype "input"))
      (node (ref "U11") (pin "1") (pinfunction "1_1") (pintype "input"))
      (node (ref "U11") (pin "2") (pinfunction "2_2") (pintype "input"))
      (node (ref "U11") (pin "3") (pinfunction "3_3") (pintype "input"))
      (node (ref "U11") (pin "4") (pinfunction "4_4") (pintype "input"))
      (node (ref "U12") (pin "1") (pinfunction "1_1") (pintype "input"))
      (node (ref "U12") (pin "2") (pinfunction "2_2") (pintype "input"))
      (node (ref "U12") (pin "3") (pinfunction "3_3") (pintype "input"))
      (node (ref "U12") (pin "4") (pinfunction "4_4") (pintype "input"))
      (node (ref "U13") (pin "1") (pinfunction "1_1") (pintype "input"))
      (node (ref "U13") (pin "2") (pinfunction "2_2") (pintype "input"))
      (node (ref "U13") (pin "3") (pinfunction "3_3") (pintype "input"))
      (node (ref "U13") (pin "4") (pinfunction "4_4") (pintype "input"))
      (node (ref "U15") (pin "4") (pinfunction "VSS_4") (pintype "unspecified"))
      (node (ref "U16") (pin "1") (pinfunction "1_1") (pintype "input"))
      (node (ref "U16") (pin "2") (pinfunction "2_2") (pintype "input"))
      (node (ref "U16") (pin "3") (pinfunction "3_3") (pintype "input"))
      (node (ref "U16") (pin "4") (pinfunction "4_4") (pintype "input"))
      (node (ref "U17") (pin "1") (pinfunction "1_1") (pintype "input"))
      (node (ref "U17") (pin "2") (pinfunction "2_2") (pintype "input"))
      (node (ref "U17") (pin "3") (pinfunction "3_3") (pintype "input"))
      (node (ref "U17") (pin "4") (pinfunction "4_4") (pintype "input"))
      (node (ref "U18") (pin "1") (pinfunction "1_1") (pintype "input"))
      (node (ref "U18") (pin "2") (pinfunction "2_2") (pintype "input"))
      (node (ref "U18") (pin "3") (pinfunction "3_3") (pintype "input"))
      (node (ref "U18") (pin "4") (pinfunction "4_4") (pintype "input"))
      (node (ref "U20") (pin "1") (pinfunction "1_1") (pintype "input"))
      (node (ref "U20") (pin "2") (pinfunction "2_2") (pintype "input"))
      (node (ref "U20") (pin "3") (pinfunction "3_3") (pintype "input"))
      (node (ref "U20") (pin "4") (pinfunction "4_4") (pintype "input"))
      (node (ref "U22") (pin "1") (pinfunction "1_1") (pintype "input"))
      (node (ref "U22") (pin "2") (pinfunction "2_2") (pintype "input"))
      (node (ref "U22") (pin "3") (pinfunction "3_3") (pintype "input"))
      (node (ref "U22") (pin "4") (pinfunction "4_4") (pintype "input"))
      (node (ref "U24") (pin "1") (pinfunction "1_1") (pintype "input"))
      (node (ref "U24") (pin "2") (pinfunction "2_2") (pintype "input"))
      (node (ref "U24") (pin "3") (pinfunction "3_3") (pintype "input"))
      (node (ref "U24") (pin "4") (pinfunction "4_4") (pintype "input"))
      (node (ref "U25") (pin "1") (pinfunction "1_1") (pintype "input"))
      (node (ref "U25") (pin "2") (pinfunction "2_2") (pintype "input"))
      (node (ref "U25") (pin "3") (pinfunction "3_3") (pintype "input"))
      (node (ref "U25") (pin "4") (pinfunction "4_4") (pintype "input"))
      (node (ref "U26") (pin "1") (pinfunction "1_1") (pintype "input"))
      (node (ref "U26") (pin "2") (pinfunction "2_2") (pintype "input"))
      (node (ref "U26") (pin "3") (pinfunction "3_3") (pintype "input"))
      (node (ref "U26") (pin "4") (pinfunction "4_4") (pintype "input"))
      (node (ref "U27") (pin "1") (pinfunction "1_1") (pintype "input"))
      (node (ref "U27") (pin "2") (pinfunction "2_2") (pintype "input"))
      (node (ref "U27") (pin "3") (pinfunction "3_3") (pintype "input"))
      (node (ref "U27") (pin "4") (pinfunction "4_4") (pintype "input"))
    )
    (net (code "4") (name "Net-(C1-Pad1)") (class "Default")
      (node (ref "C1") (pin "1") (pinfunction "1_1") (pintype "input"))
      (node (ref "U11") (pin "5") (pinfunction "5_5") (pintype "input"))
    )
    (net (code "5") (name "Net-(C1-Pad2)") (class "Default")
      (node (ref "C1") (pin "2") (pinfunction "2_2") (pintype "input"))
      (node (ref "H11") (pin "1") (pinfunction "1_1") (pintype "input"))
      (node (ref "H11") (pin "3") (pinfunction "3_3") (pintype "input"))
      (node (ref "H11") (pin "5") (pinfunction "5_5") (pintype "input"))
    )
    (net (code "6") (name "Net-(C4-Pad1)") (class "Default")
      (node (ref "C4") (pin "1") (pinfunction "1_1") (pintype "input"))
      (node (ref "H12") (pin "2") (pinfunction "2_2") (pintype "input"))
      (node (ref "H12") (pin "4") (pinfunction "4_4") (pintype "input"))
      (node (ref "H12") (pin "6") (pinfunction "6_6") (pintype "input"))
      (node (ref "R12") (pin "1") (pinfunction "1_1") (pintype "input"))
    )
    (net (code "7") (name "Net-(C4-Pad2)") (class "Default")
      (node (ref "C4") (pin "2") (pinfunction "2_2") (pintype "input"))
      (node (ref "U13") (pin "5") (pinfunction "5_5") (pintype "input"))
    )
    (net (code "8") (name "Net-(C24-Pad1)") (class "Default")
      (node (ref "C24") (pin "1") (pinfunction "1_1") (pintype "input"))
      (node (ref "U12") (pin "5") (pinfunction "5_5") (pintype "input"))
    )
    (net (code "9") (name "Net-(C28-Pad2)") (class "Default")
      (node (ref "C28") (pin "2") (pinfunction "2_2") (pintype "input"))
      (node (ref "H6") (pin "2") (pinfunction "2_2") (pintype "input"))
      (node (ref "R18") (pin "2") (pinfunction "2_2") (pintype "input"))
      (node (ref "U16") (pin "5") (pinfunction "5_5") (pintype "input"))
    )
    (net (code "10") (name "Net-(C48-Pad1)") (class "Default")
      (node (ref "C48") (pin "1") (pinfunction "1_1") (pintype "input"))
      (node (ref "R41") (pin "1") (pinfunction "1_1") (pintype "input"))
      (node (ref "R46") (pin "1") (pinfunction "1_1") (pintype "input"))
      (node (ref "R49") (pin "2") (pinfunction "2_2") (pintype "input"))
    )
    (net (code "11") (name "Net-(C48-Pad2)") (class "Default")
      (node (ref "C48") (pin "2") (pinfunction "2_2") (pintype "input"))
      (node (ref "R45") (pin "1") (pinfunction "1_1") (pintype "input"))
      (node (ref "R46") (pin "2") (pinfunction "2_2") (pintype "input"))
      (node (ref "R50") (pin "2") (pinfunction "2_2") (pintype "input"))
    )
    (net (code "12") (name "Net-(C49-Pad1)") (class "Default")
      (node (ref "C49") (pin "1") (pinfunction "1_1") (pintype "input"))
      (node (ref "R38") (pin "1") (pinfunction "1_1") (pintype "input"))
      (node (ref "R39") (pin "1") (pinfunction "1_1") (pintype "input"))
      (node (ref "R47") (pin "2") (pinfunction "2_2") (pintype "input"))
    )
    (net (code "13") (name "Net-(C50-Pad1)") (class "Default")
      (node (ref "C50") (pin "1") (pinfunction "1_1") (pintype "input"))
      (node (ref "R42") (pin "2") (pinfunction "2_2") (pintype "input"))
      (node (ref "R43") (pin "1") (pinfunction "1_1") (pintype "input"))
      (node (ref "R48") (pin "1") (pinfunction "1_1") (pintype "input"))
    )
    (net (code "14") (name "Net-(C51-Pad1)") (class "Default")
      (node (ref "C51") (pin "1") (pinfunction "1_1") (pintype "input"))
      (node (ref "H17") (pin "1") (pinfunction "1_1") (pintype "input"))
      (node (ref "R50") (pin "1") (pinfunction "1_1") (pintype "input"))
      (node (ref "U27") (pin "5") (pinfunction "5_5") (pintype "input"))
    )
    (net (code "15") (name "Net-(C52-Pad2)") (class "Default")
      (node (ref "C52") (pin "2") (pinfunction "2_2") (pintype "input"))
      (node (ref "H16") (pin "1") (pinfunction "1_1") (pintype "input"))
      (node (ref "R49") (pin "1") (pinfunction "1_1") (pintype "input"))
      (node (ref "U26") (pin "5") (pinfunction "5_5") (pintype "input"))
    )
    (net (code "16") (name "Net-(D1-A)") (class "Default")
      (node (ref "CN24") (pin "5") (pinfunction "5_5") (pintype "unspecified"))
      (node (ref "CN24") (pin "6") (pinfunction "6_6") (pintype "unspecified"))
      (node (ref "D1") (pin "2") (pinfunction "A_2") (pintype "unspecified"))
    )
    (net (code "17") (name "Net-(D2-C)") (class "Default")
      (node (ref "CN24") (pin "1") (pinfunction "1_1") (pintype "unspecified"))
      (node (ref "CN24") (pin "2") (pinfunction "2_2") (pintype "unspecified"))
      (node (ref "D2") (pin "1") (pinfunction "C_1") (pintype "unspecified"))
    )
    (net (code "18") (name "Net-(D4-A)") (class "Default")
      (node (ref "D4") (pin "2") (pinfunction "A_2") (pintype "input"))
      (node (ref "R10") (pin "2") (pinfunction "2_2") (pintype "input"))
    )
    (net (code "19") (name "Net-(D5-A)") (class "Default")
      (node (ref "D5") (pin "2") (pinfunction "A_2") (pintype "input"))
      (node (ref "R11") (pin "2") (pinfunction "2_2") (pintype "input"))
    )
    (net (code "20") (name "Net-(D6-A)") (class "Default")
      (node (ref "D6") (pin "2") (pinfunction "A_2") (pintype "input"))
      (node (ref "R21") (pin "2") (pinfunction "2_2") (pintype "input"))
    )
    (net (code "21") (name "Net-(D7-A)") (class "Default")
      (node (ref "D7") (pin "2") (pinfunction "A_2") (pintype "input"))
      (node (ref "R22") (pin "2") (pinfunction "2_2") (pintype "input"))
    )
    (net (code "22") (name "Net-(D8-A)") (class "Default")
      (node (ref "CN25") (pin "5") (pinfunction "5_5") (pintype "unspecified"))
      (node (ref "CN25") (pin "6") (pinfunction "6_6") (pintype "unspecified"))
      (node (ref "D8") (pin "2") (pinfunction "A_2") (pintype "unspecified"))
    )
    (net (code "23") (name "Net-(D9-C)") (class "Default")
      (node (ref "CN25") (pin "1") (pinfunction "1_1") (pintype "unspecified"))
      (node (ref "CN25") (pin "2") (pinfunction "2_2") (pintype "unspecified"))
      (node (ref "D9") (pin "1") (pinfunction "C_1") (pintype "unspecified"))
    )
    (net (code "24") (name "Net-(D14-A)") (class "Default")
      (node (ref "D14") (pin "2") (pinfunction "A_2") (pintype "input"))
      (node (ref "R34") (pin "2") (pinfunction "2_2") (pintype "input"))
    )
    (net (code "25") (name "Net-(D15-A)") (class "Default")
      (node (ref "D15") (pin "2") (pinfunction "A_2") (pintype "input"))
      (node (ref "R35") (pin "2") (pinfunction "2_2") (pintype "input"))
    )
    (net (code "26") (name "Net-(D16-A)") (class "Default")
      (node (ref "CN27") (pin "5") (pinfunction "5_5") (pintype "unspecified"))
      (node (ref "CN27") (pin "6") (pinfunction "6_6") (pintype "unspecified"))
      (node (ref "D16") (pin "2") (pinfunction "A_2") (pintype "unspecified"))
    )
    (net (code "27") (name "Net-(D17-C)") (class "Default")
      (node (ref "CN27") (pin "1") (pinfunction "1_1") (pintype "unspecified"))
      (node (ref "CN27") (pin "2") (pinfunction "2_2") (pintype "unspecified"))
      (node (ref "D17") (pin "1") (pinfunction "C_1") (pintype "unspecified"))
    )
    (net (code "28") (name "Net-(D22-A)") (class "Default")
      (node (ref "D22") (pin "2") (pinfunction "A_2") (pintype "input"))
      (node (ref "R53") (pin "2") (pinfunction "2_2") (pintype "input"))
    )
    (net (code "29") (name "Net-(D23-A)") (class "Default")
      (node (ref "D23") (pin "2") (pinfunction "A_2") (pintype "input"))
      (node (ref "R54") (pin "2") (pinfunction "2_2") (pintype "input"))
    )
    (net (code "30") (name "Net-(D24-A)") (class "Default")
      (node (ref "CN29") (pin "5") (pinfunction "5_5") (pintype "unspecified"))
      (node (ref "CN29") (pin "6") (pinfunction "6_6") (pintype "unspecified"))
      (node (ref "D24") (pin "2") (pinfunction "A_2") (pintype "unspecified"))
    )
    (net (code "31") (name "Net-(D25-C)") (class "Default")
      (node (ref "CN29") (pin "1") (pinfunction "1_1") (pintype "unspecified"))
      (node (ref "CN29") (pin "2") (pinfunction "2_2") (pintype "unspecified"))
      (node (ref "D25") (pin "1") (pinfunction "C_1") (pintype "unspecified"))
    )
    (net (code "32") (name "Net-(H2-Pad1)") (class "Default")
      (node (ref "H2") (pin "1") (pinfunction "1_1") (pintype "unspecified"))
      (node (ref "PR7") (pin "1") (pinfunction "1_1") (pintype "input"))
    )
    (net (code "33") (name "Net-(H7-Pad2)") (class "Default")
      (node (ref "H7") (pin "2") (pinfunction "2_2") (pintype "input"))
      (node (ref "R13") (pin "1") (pinfunction "1_1") (pintype "input"))
      (node (ref "U17") (pin "5") (pinfunction "5_5") (pintype "input"))
    )
    (net (code "34") (name "Net-(H8-Pad2)") (class "Default")
      (node (ref "H8") (pin "2") (pinfunction "2_2") (pintype "input"))
      (node (ref "R14") (pin "1") (pinfunction "1_1") (pintype "input"))
      (node (ref "U18") (pin "5") (pinfunction "5_5") (pintype "input"))
    )
    (net (code "35") (name "Net-(H9-Pad1)") (class "Default")
      (node (ref "H9") (pin "1") (pinfunction "1_1") (pintype "input"))
      (node (ref "R27") (pin "1") (pinfunction "1_1") (pintype "input"))
      (node (ref "U20") (pin "5") (pinfunction "5_5") (pintype "input"))
    )
    (net (code "36") (name "Net-(H11-Pad2)") (class "Default")
      (node (ref "H11") (pin "2") (pinfunction "2_2") (pintype "input"))
      (node (ref "PR3") (pin "1") (pinfunction "1_1") (pintype "input"))
      (node (ref "PR3") (pin "2") (pinfunction "2_2") (pintype "input"))
      (node (ref "R2") (pin "1") (pinfunction "1_1") (pintype "input"))
    )
    (net (code "37") (name "Net-(H11-Pad4)") (class "Default")
      (node (ref "H11") (pin "4") (pinfunction "4_4") (pintype "input"))
      (node (ref "R1") (pin "1") (pinfunction "1_1") (pintype "input"))
    )
    (net (code "38") (name "Net-(H13-Pad1)") (class "Default")
      (node (ref "H13") (pin "1") (pinfunction "1_1") (pintype "input"))
      (node (ref "R47") (pin "1") (pinfunction "1_1") (pintype "input"))
      (node (ref "U24") (pin "5") (pinfunction "5_5") (pintype "input"))
    )
    (net (code "39") (name "Net-(H14-Pad1)") (class "Default")
      (node (ref "H14") (pin "1") (pinfunction "1_1") (pintype "input"))
      (node (ref "R48") (pin "2") (pinfunction "2_2") (pintype "input"))
      (node (ref "U25") (pin "5") (pinfunction "5_5") (pintype "input"))
    )
    (net (code "40") (name "Net-(PR1-Pad1)") (class "Default")
      (node (ref "PR1") (pin "1") (pinfunction "1_1") (pintype "input"))
      (node (ref "R17") (pin "1") (pinfunction "1_1") (pintype "input"))
    )
    (net (code "41") (name "Net-(PR1-Pad2)") (class "Default")
      (node (ref "PR1") (pin "2") (pinfunction "2_2") (pintype "input"))
      (node (ref "R15") (pin "1") (pinfunction "1_1") (pintype "input"))
    )
    (net (code "42") (name "Net-(PR1-Pad3)") (class "Default")
      (node (ref "PR1") (pin "3") (pinfunction "3_3") (pintype "input"))
      (node (ref "R16") (pin "1") (pinfunction "1_1") (pintype "input"))
    )
    (net (code "43") (name "Net-(PR14-Pad3)") (class "Default")
      (node (ref "PR14") (pin "3") (pinfunction "3_3") (pintype "input"))
      (node (ref "R31") (pin "1") (pinfunction "1_1") (pintype "input"))
    )
    (net (code "44") (name "Net-(PR15-Pad1)") (class "Default")
      (node (ref "PR15") (pin "1") (pinfunction "1_1") (pintype "input"))
      (node (ref "R36") (pin "1") (pinfunction "1_1") (pintype "input"))
    )
    (net (code "45") (name "Net-(PR15-Pad2)") (class "Default")
      (node (ref "PR15") (pin "2") (pinfunction "2_2") (pintype "input"))
      (node (ref "R25") (pin "1") (pinfunction "1_1") (pintype "input"))
    )
    (net (code "46") (name "Net-(PR15-Pad3)") (class "Default")
      (node (ref "PR15") (pin "3") (pinfunction "3_3") (pintype "input"))
      (node (ref "R37") (pin "2") (pinfunction "2_2") (pintype "input"))
    )
    (net (code "47") (name "Net-(PR16-Pad1)") (class "Default")
      (node (ref "PR16") (pin "1") (pinfunction "1_1") (pintype "input"))
      (node (ref "R56") (pin "1") (pinfunction "1_1") (pintype "input"))
      (node (ref "R57") (pin "2") (pinfunction "2_2") (pintype "input"))
    )
    (net (code "48") (name "Net-(PR16-Pad3)") (class "Default")
      (node (ref "PR16") (pin "3") (pinfunction "3_3") (pintype "input"))
      (node (ref "R55") (pin "2") (pinfunction "2_2") (pintype "input"))
    )
    (net (code "49") (name "Net-(R23-Pad1)") (class "Default")
      (node (ref "R23") (pin "1") (pinfunction "1_1") (pintype "input"))
      (node (ref "R24") (pin "2") (pinfunction "2_2") (pintype "input"))
      (node (ref "R25") (pin "2") (pinfunction "2_2") (pintype "input"))
    )
    (net (code "50") (name "Net-(U1-+IN)") (class "Default")
      (node (ref "R3") (pin "1") (pinfunction "1_1") (pintype "input"))
      (node (ref "U1") (pin "5") (pinfunction "+IN_5") (pintype "input"))
    )
    (net (code "51") (name "Net-(U1--IN)") (class "Default")
      (node (ref "PR13") (pin "2") (pinfunction "2_2") (pintype "input"))
      (node (ref "PR13") (pin "3") (pinfunction "3_3") (pintype "input"))
      (node (ref "R12") (pin "2") (pinfunction "2_2") (pintype "input"))
      (node (ref "R5") (pin "1") (pinfunction "1_1") (pintype "input"))
      (node (ref "U1") (pin "6") (pinfunction "-IN_6") (pintype "input"))
    )
    (net (code "52") (name "Net-(U1-B_Vo)") (class "Default")
      (node (ref "C3") (pin "1") (pinfunction "1_1") (pintype "input"))
      (node (ref "H12") (pin "5") (pinfunction "5_5") (pintype "input"))
      (node (ref "PR6") (pin "3") (pinfunction "3_3") (pintype "input"))
      (node (ref "R7") (pin "2") (pinfunction "2_2") (pintype "input"))
      (node (ref "U1") (pin "8") (pinfunction "B_Vo_8") (pintype "input"))
    )
    (net (code "53") (name "Net-(U1-H-Vo)") (class "Default")
      (node (ref "H12") (pin "3") (pinfunction "3_3") (pintype "input"))
      (node (ref "PR4") (pin "2") (pinfunction "2_2") (pintype "input"))
      (node (ref "R6") (pin "1") (pinfunction "1_1") (pintype "input"))
      (node (ref "U1") (pin "14") (pinfunction "H-Vo_14") (pintype "input"))
    )
    (net (code "54") (name "Net-(U1-L_Vo)") (class "Default")
      (node (ref "C2") (pin "2") (pinfunction "2_2") (pintype "input"))
      (node (ref "H12") (pin "1") (pinfunction "1_1") (pintype "input"))
      (node (ref "U1") (pin "1") (pinfunction "L_Vo_1") (pintype "input"))
    )
    (net (code "55") (name "Net-(U1-Vin1)") (class "Default")
      (node (ref "R1") (pin "2") (pinfunction "2_2") (pintype "input"))
      (node (ref "U1") (pin "13") (pinfunction "Vin1_13") (pintype "input"))
    )
    (net (code "56") (name "Net-(U1-Vin2)") (class "Default")
      (node (ref "PR3") (pin "3") (pinfunction "3_3") (pintype "input"))
      (node (ref "PR9") (pin "2") (pinfunction "2_2") (pintype "input"))
      (node (ref "PR9") (pin "3") (pinfunction "3_3") (pintype "input"))
      (node (ref "R2") (pin "2") (pinfunction "2_2") (pintype "input"))
      (node (ref "R4") (pin "2") (pinfunction "2_2") (pintype "input"))
      (node (ref "U1") (pin "4") (pinfunction "Vin2_4") (pintype "input"))
    )
    (net (code "57") (name "Net-(U1-Vin3)") (class "Default")
      (node (ref "H11") (pin "6") (pinfunction "6_6") (pintype "input"))
      (node (ref "U1") (pin "3") (pinfunction "Vin3_3") (pintype "input"))
    )
    (net (code "58") (name "Net-(U1-Vo)") (class "Default")
      (node (ref "C24") (pin "2") (pinfunction "2_2") (pintype "input"))
      (node (ref "PR13") (pin "1") (pinfunction "1_1") (pintype "input"))
      (node (ref "R5") (pin "2") (pinfunction "2_2") (pintype "input"))
      (node (ref "U1") (pin "7") (pinfunction "Vo_7") (pintype "input"))
    )
    (net (code "59") (name "Net-(U1-adj1)") (class "Default")
      (node (ref "C3") (pin "2") (pinfunction "2_2") (pintype "input"))
      (node (ref "PR4") (pin "1") (pinfunction "1_1") (pintype "input"))
      (node (ref "R6") (pin "2") (pinfunction "2_2") (pintype "input"))
      (node (ref "U1") (pin "9") (pinfunction "adj1_9") (pintype "input"))
    )
    (net (code "60") (name "Net-(U1-adj2)") (class "Default")
      (node (ref "C2") (pin "1") (pinfunction "1_1") (pintype "input"))
      (node (ref "PR6") (pin "2") (pinfunction "2_2") (pintype "input"))
      (node (ref "R7") (pin "1") (pinfunction "1_1") (pintype "input"))
      (node (ref "U1") (pin "16") (pinfunction "adj2_16") (pintype "input"))
    )
    (net (code "61") (name "Net-(U14-+IN)") (class "Default")
      (node (ref "C26") (pin "2") (pinfunction "2_2") (pintype "input"))
      (node (ref "R14") (pin "2") (pinfunction "2_2") (pintype "input"))
      (node (ref "R59") (pin "1") (pinfunction "1_1") (pintype "input"))
      (node (ref "U14") (pin "3") (pinfunction "+IN_3") (pintype "unspecified"))
    )
    (net (code "62") (name "Net-(U14--IN)") (class "Default")
      (node (ref "C25") (pin "1") (pinfunction "1_1") (pintype "input"))
      (node (ref "R13") (pin "2") (pinfunction "2_2") (pintype "input"))
      (node (ref "R19") (pin "1") (pinfunction "1_1") (pintype "input"))
      (node (ref "R59") (pin "2") (pinfunction "2_2") (pintype "input"))
      (node (ref "U14") (pin "2") (pinfunction "-IN_2") (pintype "unspecified"))
    )
    (net (code "63") (name "Net-(U14--VS)") (class "Default")
      (node (ref "C35") (pin "2") (pinfunction "2_2") (pintype "input"))
      (node (ref "R58") (pin "2") (pinfunction "2_2") (pintype "input"))
      (node (ref "U14") (pin "4") (pinfunction "-VS_4") (pintype "unspecified"))
    )
    (net (code "64") (name "Net-(U14-OUTPUT)") (class "Default")
      (node (ref "R18") (pin "1") (pinfunction "1_1") (pintype "input"))
      (node (ref "U14") (pin "6") (pinfunction "OUTPUT_6") (pintype "unspecified"))
    )
    (net (code "65") (name "Net-(U14-REF)") (class "Default")
      (node (ref "C27") (pin "2") (pinfunction "2_2") (pintype "input"))
      (node (ref "R15") (pin "2") (pinfunction "2_2") (pintype "input"))
      (node (ref "U14") (pin "5") (pinfunction "REF_5") (pintype "unspecified"))
    )
    (net (code "66") (name "Net-(U14-RG)") (class "Default")
      (node (ref "PR7") (pin "2") (pinfunction "2_2") (pintype "input"))
      (node (ref "PR7") (pin "3") (pinfunction "3_3") (pintype "input"))
      (node (ref "R20") (pin "2") (pinfunction "2_2") (pintype "input"))
      (node (ref "U14") (pin "8") (pinfunction "RG_8") (pintype "unspecified"))
    )
    (net (code "67") (name "Net-(U14-RG{slash}2)") (class "Default")
      (node (ref "H2") (pin "2") (pinfunction "2_2") (pintype "unspecified"))
      (node (ref "U14") (pin "1") (pinfunction "RG/2_1") (pintype "unspecified"))
    )
    (net (code "68") (name "Net-(U15-CS#)") (class "Default")
      (node (ref "H3") (pin "4") (pinfunction "4_4") (pintype "unspecified"))
      (node (ref "U15") (pin "1") (pinfunction "CS#_1") (pintype "unspecified"))
    )
    (net (code "69") (name "Net-(U15-PA0)") (class "Default")
      (node (ref "H2") (pin "3") (pinfunction "3_3") (pintype "unspecified"))
      (node (ref "U15") (pin "5") (pinfunction "PA0_5") (pintype "unspecified"))
    )
    (net (code "70") (name "Net-(U15-PW0)") (class "Default")
      (node (ref "R20") (pin "1") (pinfunction "1_1") (pintype "input"))
      (node (ref "U15") (pin "6") (pinfunction "PW0_6") (pintype "unspecified"))
    )
    (net (code "71") (name "Net-(U15-SCK)") (class "Default")
      (node (ref "H3") (pin "3") (pinfunction "3_3") (pintype "unspecified"))
      (node (ref "U15") (pin "2") (pinfunction "SCK_2") (pintype "unspecified"))
    )
    (net (code "72") (name "Net-(U15-SI)") (class "Default")
      (node (ref "H3") (pin "2") (pinfunction "2_2") (pintype "unspecified"))
      (node (ref "U15") (pin "3") (pinfunction "SI_3") (pintype "unspecified"))
    )
    (net (code "73") (name "Net-(U19A-IN1+)") (class "Default")
      (node (ref "R23") (pin "2") (pinfunction "2_2") (pintype "input"))
      (node (ref "U19") (pin "3") (pinfunction "IN1+_3") (pintype "unspecified"))
    )
    (net (code "74") (name "Net-(U19A-IN1-)") (class "Default")
      (node (ref "R26") (pin "2") (pinfunction "2_2") (pintype "input"))
      (node (ref "R27") (pin "2") (pinfunction "2_2") (pintype "input"))
      (node (ref "R28") (pin "1") (pinfunction "1_1") (pintype "input"))
      (node (ref "U19") (pin "2") (pinfunction "IN1-_2") (pintype "unspecified"))
    )
    (net (code "75") (name "Net-(U19A-OUT1)") (class "Default")
      (node (ref "R28") (pin "2") (pinfunction "2_2") (pintype "input"))
      (node (ref "R30") (pin "2") (pinfunction "2_2") (pintype "input"))
      (node (ref "U19") (pin "1") (pinfunction "OUT1_1") (pintype "output"))
    )
    (net (code "76") (name "Net-(U19B-IN2+)") (class "Default")
      (node (ref "R29") (pin "2") (pinfunction "2_2") (pintype "input"))
      (node (ref "U19") (pin "5") (pinfunction "IN2+_5") (pintype "unspecified"))
    )
    (net (code "77") (name "Net-(U19B-IN2-)") (class "Default")
      (node (ref "R30") (pin "1") (pinfunction "1_1") (pintype "input"))
      (node (ref "R31") (pin "2") (pinfunction "2_2") (pintype "input"))
      (node (ref "U19") (pin "6") (pinfunction "IN2-_6") (pintype "unspecified"))
    )
    (net (code "78") (name "Net-(U19B-OUT2)") (class "Default")
      (node (ref "H10") (pin "1") (pinfunction "1_1") (pintype "input"))
      (node (ref "PR14") (pin "2") (pinfunction "2_2") (pintype "input"))
      (node (ref "U19") (pin "7") (pinfunction "OUT2_7") (pintype "output"))
      (node (ref "U22") (pin "5") (pinfunction "5_5") (pintype "input"))
    )
    (net (code "79") (name "Net-(U23-+OUT)") (class "Default")
      (node (ref "C46") (pin "2") (pinfunction "2_2") (pintype "input"))
      (node (ref "R40") (pin "2") (pinfunction "2_2") (pintype "input"))
      (node (ref "R41") (pin "2") (pinfunction "2_2") (pintype "input"))
      (node (ref "U23") (pin "4") (pinfunction "+OUT_4") (pintype "unspecified"))
    )
    (net (code "80") (name "Net-(U23-–OUT)") (class "Default")
      (node (ref "C47") (pin "1") (pinfunction "1_1") (pintype "input"))
      (node (ref "R44") (pin "1") (pinfunction "1_1") (pintype "input"))
      (node (ref "R45") (pin "2") (pinfunction "2_2") (pintype "input"))
      (node (ref "U23") (pin "5") (pinfunction "–OUT_5") (pintype "unspecified"))
    )
    (net (code "81") (name "OUT+") (class "Default")
      (node (ref "C46") (pin "1") (pinfunction "1_1") (pintype "input"))
      (node (ref "R39") (pin "2") (pinfunction "2_2") (pintype "input"))
      (node (ref "R40") (pin "1") (pinfunction "1_1") (pintype "input"))
      (node (ref "U23") (pin "1") (pinfunction "–IN_1") (pintype "unspecified"))
    )
    (net (code "82") (name "OUT-") (class "Default")
      (node (ref "C47") (pin "2") (pinfunction "2_2") (pintype "input"))
      (node (ref "R42") (pin "1") (pinfunction "1_1") (pintype "input"))
      (node (ref "R44") (pin "2") (pinfunction "2_2") (pintype "input"))
      (node (ref "U23") (pin "8") (pinfunction "+IN_8") (pintype "unspecified"))
    )
    (net (code "83") (name "V+") (class "Default")
      (node (ref "U23") (pin "3") (pinfunction "V+_3") (pintype "unspecified"))
    )
    (net (code "84") (name "V-") (class "Default")
      (node (ref "U23") (pin "6") (pinfunction "V–_6") (pintype "unspecified"))
    )
    (net (code "85") (name "VCOM") (class "Default")
      (node (ref "C61") (pin "2") (pinfunction "2_2") (pintype "input"))
      (node (ref "H15") (pin "2") (pinfunction "2_2") (pintype "unspecified"))
      (node (ref "U23") (pin "2") (pinfunction "VOCM_2") (pintype "unspecified"))
    )
    (net (code "86") (name "V_COM") (class "Default")
      (node (ref "H15") (pin "1") (pinfunction "1_1") (pintype "unspecified"))
      (node (ref "PR16") (pin "2") (pinfunction "2_2") (pintype "input"))
    )
    (net (code "87") (name "unconnected-(PR4-Pad3)") (class "Default")
      (node (ref "PR4") (pin "3") (pinfunction "3_3") (pintype "input"))
    )
    (net (code "88") (name "unconnected-(PR6-Pad1)") (class "Default")
      (node (ref "PR6") (pin "1") (pinfunction "1_1") (pintype "input"))
    )
    (net (code "89") (name "unconnected-(PR14-Pad1)") (class "Default")
      (node (ref "PR14") (pin "1") (pinfunction "1_1") (pintype "input"))
    )
    (net (code "90") (name "unconnected-(SCREW1-Pad1)") (class "Default")
      (node (ref "SCREW1") (pin "1") (pinfunction "1_1") (pintype "input"))
    )
    (net (code "91") (name "unconnected-(SCREW3-Pad1)") (class "Default")
      (node (ref "SCREW3") (pin "1") (pinfunction "1_1") (pintype "input"))
    )
    (net (code "92") (name "unconnected-(SCREW4-Pad1)") (class "Default")
      (node (ref "SCREW4") (pin "1") (pinfunction "1_1") (pintype "input"))
    )
    (net (code "93") (name "unconnected-(SCREW5-Pad1)") (class "Default")
      (node (ref "SCREW5") (pin "1") (pinfunction "1_1") (pintype "input"))
    )
    (net (code "94") (name "unconnected-(SCREW6-Pad1)") (class "Default")
      (node (ref "SCREW6") (pin "1") (pinfunction "1_1") (pintype "input"))
    )
    (net (code "95") (name "unconnected-(SCREW8-Pad1)") (class "Default")
      (node (ref "SCREW8") (pin "1") (pinfunction "1_1") (pintype "input"))
    )
    (net (code "96") (name "unconnected-(SCREW9-Pad1)") (class "Default")
      (node (ref "SCREW9") (pin "1") (pinfunction "1_1") (pintype "input"))
    )
    (net (code "97") (name "unconnected-(SCREW10-Pad1)") (class "Default")
      (node (ref "SCREW10") (pin "1") (pinfunction "1_1") (pintype "input"))
    )
    (net (code "98") (name "unconnected-(SCREW11-Pad1)") (class "Default")
      (node (ref "SCREW11") (pin "1") (pinfunction "1_1") (pintype "input"))
    )
    (net (code "99") (name "unconnected-(SCREW13-Pad1)") (class "Default")
      (node (ref "SCREW13") (pin "1") (pinfunction "1_1") (pintype "input"))
    )
    (net (code "100") (name "unconnected-(SCREW14-Pad1)") (class "Default")
      (node (ref "SCREW14") (pin "1") (pinfunction "1_1") (pintype "input"))
    )
    (net (code "101") (name "unconnected-(SCREW15-Pad1)") (class "Default")
      (node (ref "SCREW15") (pin "1") (pinfunction "1_1") (pintype "input"))
    )
    (net (code "102") (name "unconnected-(SCREW16-Pad1)") (class "Default")
      (node (ref "SCREW16") (pin "1") (pinfunction "1_1") (pintype "input"))
    )
    (net (code "103") (name "unconnected-(SCREW18-Pad1)") (class "Default")
      (node (ref "SCREW18") (pin "1") (pinfunction "1_1") (pintype "input"))
    )
    (net (code "104") (name "unconnected-(SCREW19-Pad1)") (class "Default")
      (node (ref "SCREW19") (pin "1") (pinfunction "1_1") (pintype "input"))
    )
    (net (code "105") (name "unconnected-(SCREW20-Pad1)") (class "Default")
      (node (ref "SCREW20") (pin "1") (pinfunction "1_1") (pintype "input"))
    )
    (net (code "106") (name "unconnected-(U1-NC-Pad2)") (class "Default")
      (node (ref "U1") (pin "2") (pinfunction "NC_2") (pintype "input+no_connect"))
    )
    (net (code "107") (name "unconnected-(U1-NC-Pad15)") (class "Default")
      (node (ref "U1") (pin "15") (pinfunction "NC_15") (pintype "input+no_connect"))
    )
    (net (code "108") (name "unconnected-(U15-PB0-Pad7)") (class "Default")
      (node (ref "U15") (pin "7") (pinfunction "PB0_7") (pintype "unspecified+no_connect"))
    )
    (net (code "109") (name "unconnected-(U23-NIC-Pad7)") (class "Default")
      (node (ref "U23") (pin "7") (pinfunction "NIC_7") (pintype "unspecified"))
    )
  )
)
